# PC_Pump_Controller_2021-02-13_17-24-19.net
KiCad netlist of a schematic drawn in EasyEDA
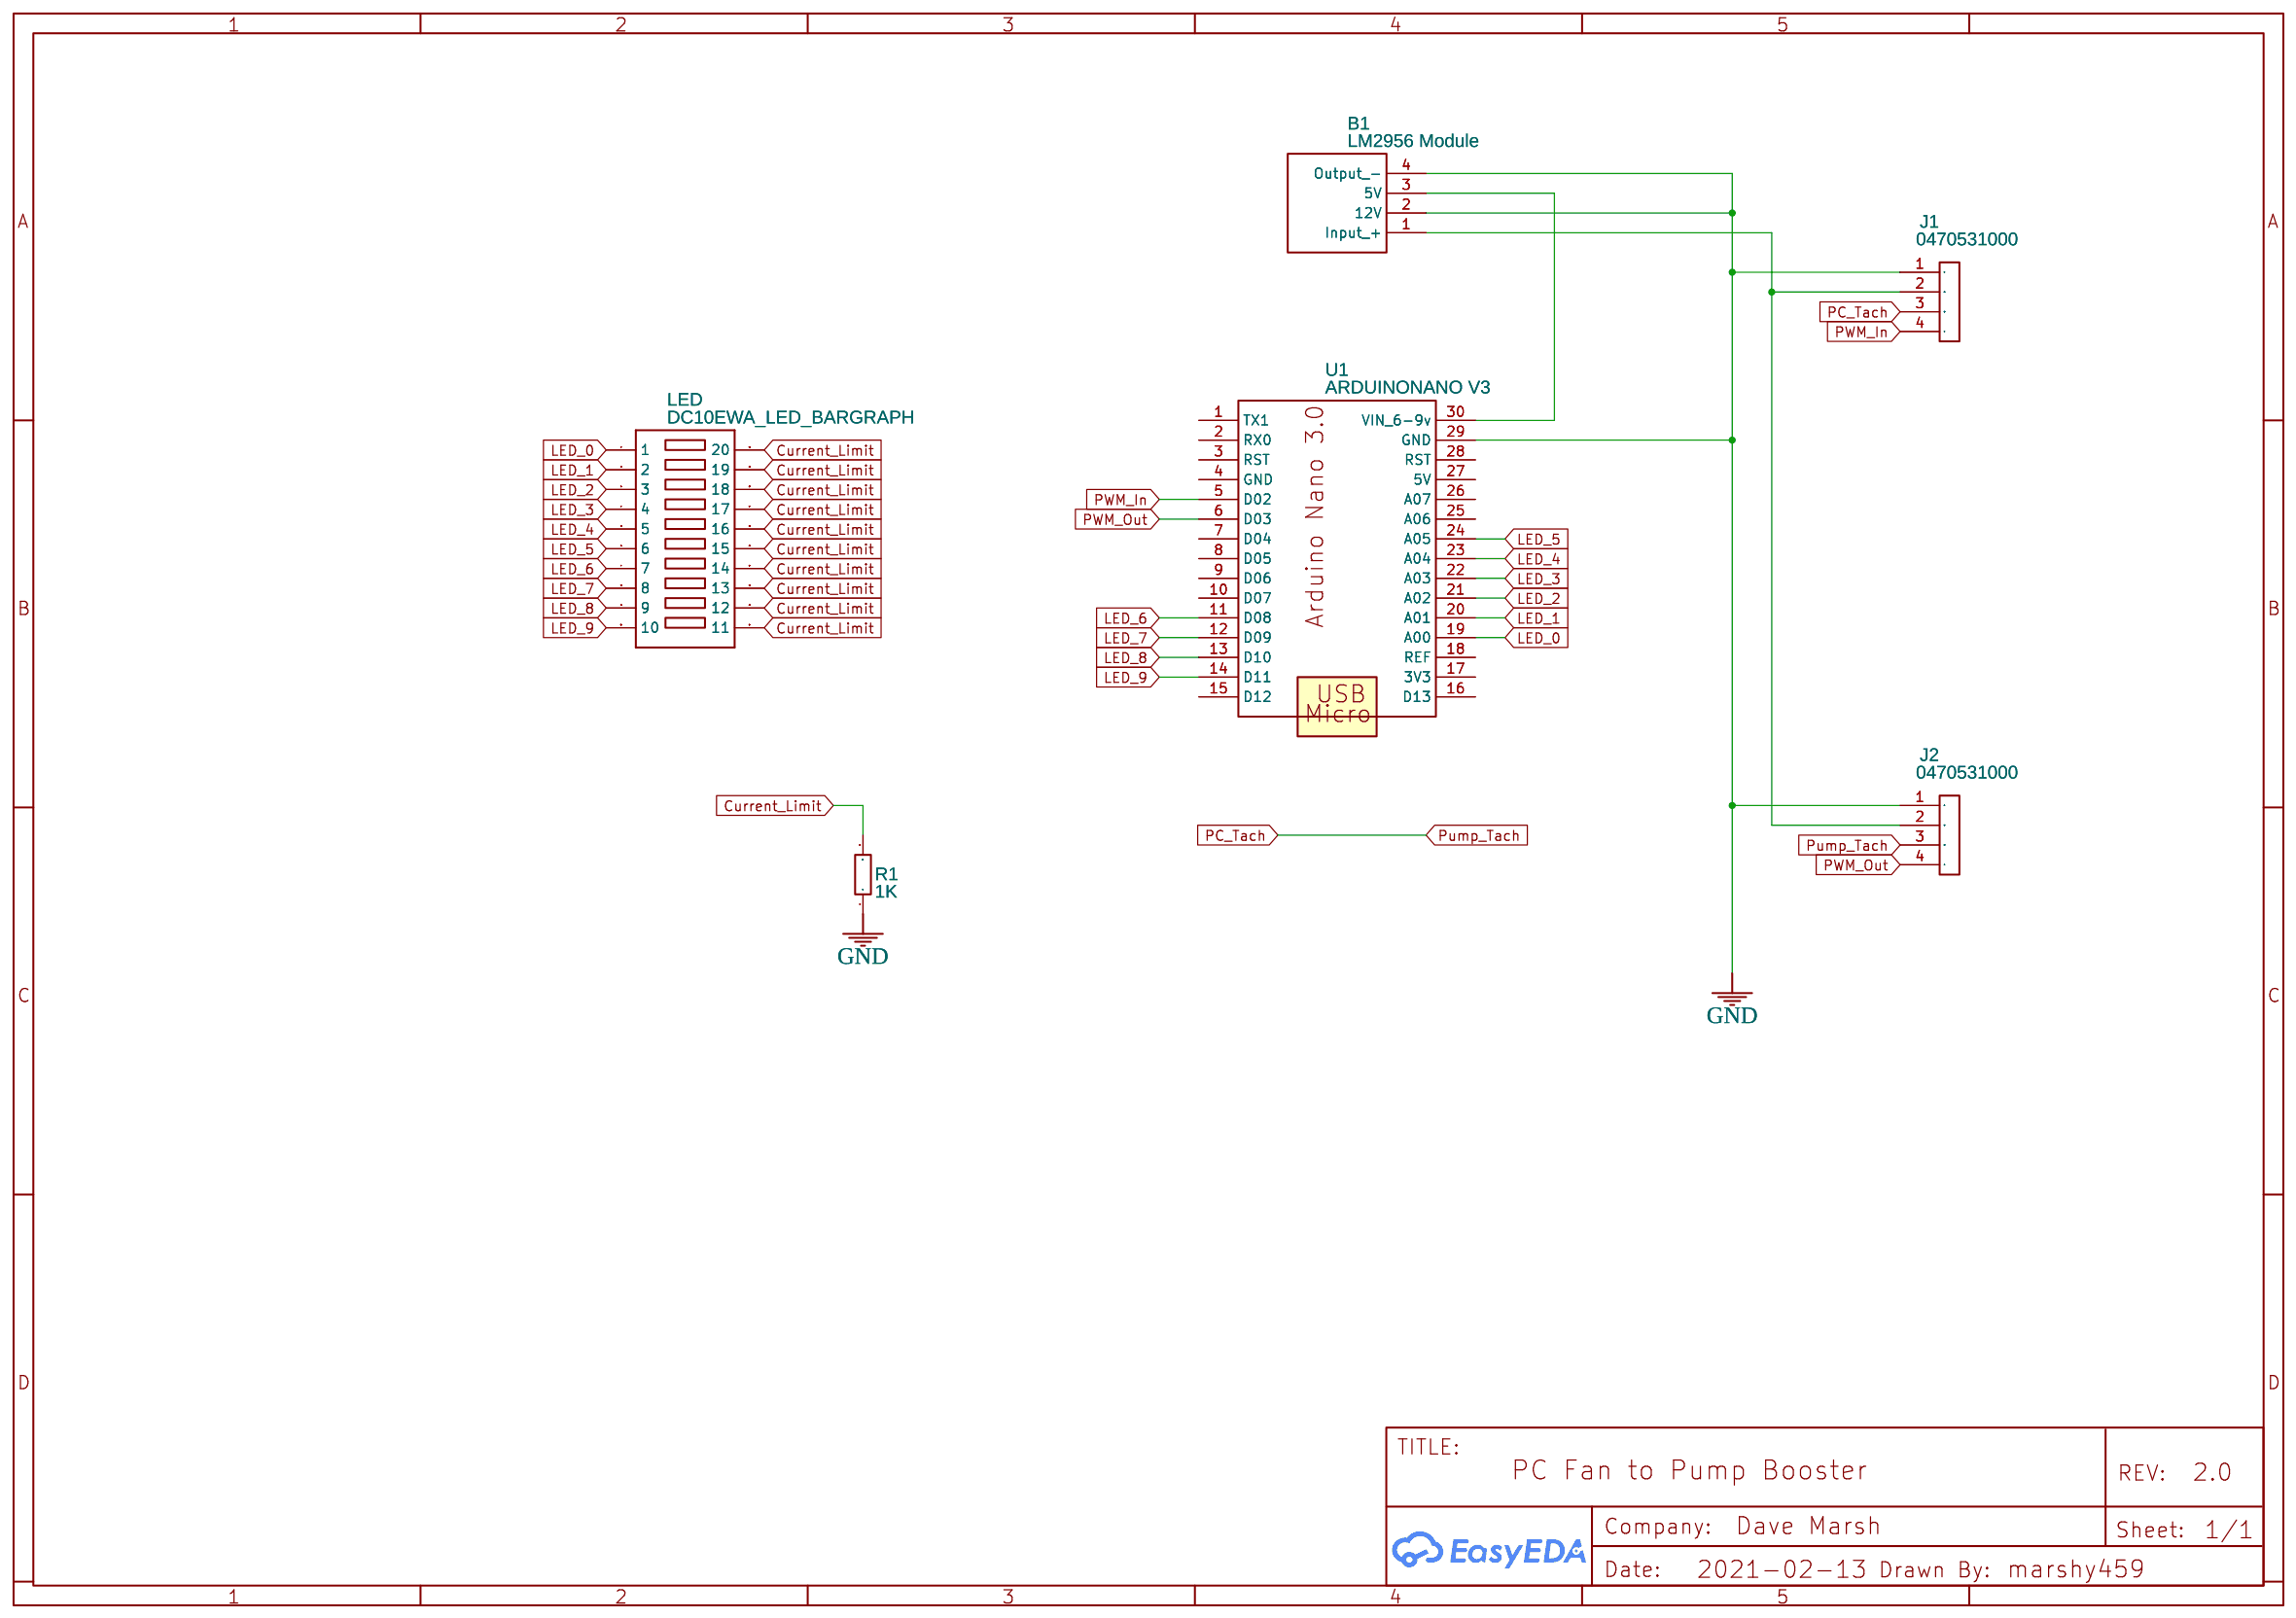
[diagram p0: schematic sheet]

(export (version "E")
  (design (tool "Eeschema 10.0.6"))
  (components
    (comp (ref "B1") (value "LM2956 Module") (libsource (lib "") (part "LM2956 Module")))
    (comp (ref "J1")
      (value "0470531000")
      (fields (field (name "BOM_Supplier Part") "WM4330-ND"))
      (libsource (lib "") (part "0470531000"))
    )
    (comp (ref "J2")
      (value "0470531000")
      (fields (field (name "BOM_Supplier Part") "WM4330-ND"))
      (libsource (lib "") (part "0470531000"))
    )
    (comp (ref "LED") (value "DC10EWA_LED_BARGRAPH") (libsource (lib "") (part "DC10EWA_LED_BARGRAPH")))
    (comp (ref "R1")
      (value "1K")
      (fields
        (field (name "BOM_Manufacturer Part") "RC1206FR-071K5L")
        (field (name "BOM_Supplier Part") "311-1.50KFRCT-ND")
      )
      (libsource (lib "") (part "RESISTOR 1K5 1206 YAGEO"))
    )
    (comp (ref "U1")
      (value "ARDUINONANO V3")
      (fields (field (name "BOM_Manufacturer Part") "ArduinoNanov3"))
      (libsource (lib "") (part "ARDUINONANO V3"))
    )
  )
  (nets
    (net (code "1") (name "Current_Limit") (class "Default")
      (node (ref "LED") (pin "11") (pinfunction "11_11") (pintype "unspecified"))
      (node (ref "LED") (pin "12") (pinfunction "12_12") (pintype "unspecified"))
      (node (ref "LED") (pin "13") (pinfunction "13_13") (pintype "input"))
      (node (ref "LED") (pin "14") (pinfunction "14_14") (pintype "input"))
      (node (ref "LED") (pin "15") (pinfunction "15_15") (pintype "input"))
      (node (ref "LED") (pin "16") (pinfunction "16_16") (pintype "input"))
      (node (ref "LED") (pin "17") (pinfunction "17_17") (pintype "input"))
      (node (ref "LED") (pin "18") (pinfunction "18_18") (pintype "input"))
      (node (ref "LED") (pin "19") (pinfunction "19_19") (pintype "input"))
      (node (ref "LED") (pin "20") (pinfunction "20_20") (pintype "input"))
      (node (ref "R1") (pin "2") (pinfunction "2_2") (pintype "unspecified"))
    )
    (net (code "2") (name "GND") (class "Default")
      (node (ref "B1") (pin "2") (pinfunction "12V_2") (pintype "unspecified"))
      (node (ref "B1") (pin "4") (pinfunction "Output_-_4") (pintype "unspecified"))
      (node (ref "J1") (pin "1") (pinfunction "1_1") (pintype "unspecified"))
      (node (ref "J2") (pin "1") (pinfunction "1_1") (pintype "unspecified"))
      (node (ref "R1") (pin "1") (pinfunction "1_1") (pintype "unspecified"))
      (node (ref "U1") (pin "29") (pinfunction "GND_29") (pintype "unspecified"))
    )
    (net (code "3") (name "LED_0") (class "Default")
      (node (ref "LED") (pin "1") (pinfunction "1_1") (pintype "input"))
      (node (ref "U1") (pin "19") (pinfunction "A00_19") (pintype "unspecified"))
    )
    (net (code "4") (name "LED_1") (class "Default")
      (node (ref "LED") (pin "2") (pinfunction "2_2") (pintype "input"))
      (node (ref "U1") (pin "20") (pinfunction "A01_20") (pintype "unspecified"))
    )
    (net (code "5") (name "LED_2") (class "Default")
      (node (ref "LED") (pin "3") (pinfunction "3_3") (pintype "input"))
      (node (ref "U1") (pin "21") (pinfunction "A02_21") (pintype "unspecified"))
    )
    (net (code "6") (name "LED_3") (class "Default")
      (node (ref "LED") (pin "4") (pinfunction "4_4") (pintype "input"))
      (node (ref "U1") (pin "22") (pinfunction "A03_22") (pintype "unspecified"))
    )
    (net (code "7") (name "LED_4") (class "Default")
      (node (ref "LED") (pin "5") (pinfunction "5_5") (pintype "input"))
      (node (ref "U1") (pin "23") (pinfunction "A04_23") (pintype "unspecified"))
    )
    (net (code "8") (name "LED_5") (class "Default")
      (node (ref "LED") (pin "6") (pinfunction "6_6") (pintype "input"))
      (node (ref "U1") (pin "24") (pinfunction "A05_24") (pintype "unspecified"))
    )
    (net (code "9") (name "LED_6") (class "Default")
      (node (ref "LED") (pin "7") (pinfunction "7_7") (pintype "input"))
      (node (ref "U1") (pin "11") (pinfunction "D08_11") (pintype "unspecified"))
    )
    (net (code "10") (name "LED_7") (class "Default")
      (node (ref "LED") (pin "8") (pinfunction "8_8") (pintype "input"))
      (node (ref "U1") (pin "12") (pinfunction "D09_12") (pintype "unspecified"))
    )
    (net (code "11") (name "LED_8") (class "Default")
      (node (ref "LED") (pin "9") (pinfunction "9_9") (pintype "unspecified"))
      (node (ref "U1") (pin "13") (pinfunction "D10_13") (pintype "unspecified"))
    )
    (net (code "12") (name "LED_9") (class "Default")
      (node (ref "LED") (pin "10") (pinfunction "10_10") (pintype "unspecified"))
      (node (ref "U1") (pin "14") (pinfunction "D11_14") (pintype "unspecified"))
    )
    (net (code "13") (name "Net-(B1-5V)") (class "Default")
      (node (ref "B1") (pin "3") (pinfunction "5V_3") (pintype "unspecified"))
      (node (ref "U1") (pin "30") (pinfunction "VIN_6-9v_30") (pintype "unspecified"))
    )
    (net (code "14") (name "Net-(B1-Input_+)") (class "Default")
      (node (ref "B1") (pin "1") (pinfunction "Input_+_1") (pintype "unspecified"))
      (node (ref "J1") (pin "2") (pinfunction "2_2") (pintype "unspecified"))
      (node (ref "J2") (pin "2") (pinfunction "2_2") (pintype "unspecified"))
    )
    (net (code "15") (name "PC_Tach") (class "Default")
      (node (ref "J1") (pin "3") (pinfunction "3_3") (pintype "unspecified"))
      (node (ref "J2") (pin "3") (pinfunction "3_3") (pintype "unspecified"))
    )
    (net (code "16") (name "PWM_In") (class "Default")
      (node (ref "J1") (pin "4") (pinfunction "4_4") (pintype "unspecified"))
      (node (ref "U1") (pin "5") (pinfunction "D02_5") (pintype "unspecified"))
    )
    (net (code "17") (name "PWM_Out") (class "Default")
      (node (ref "J2") (pin "4") (pinfunction "4_4") (pintype "unspecified"))
      (node (ref "U1") (pin "6") (pinfunction "D03_6") (pintype "unspecified"))
    )
    (net (code "18") (name "unconnected-(U1-3V3-Pad17)") (class "Default")
      (node (ref "U1") (pin "17") (pinfunction "3V3_17") (pintype "unspecified"))
    )
    (net (code "19") (name "unconnected-(U1-5V-Pad27)") (class "Default")
      (node (ref "U1") (pin "27") (pinfunction "5V_27") (pintype "unspecified"))
    )
    (net (code "20") (name "unconnected-(U1-A06-Pad25)") (class "Default")
      (node (ref "U1") (pin "25") (pinfunction "A06_25") (pintype "unspecified"))
    )
    (net (code "21") (name "unconnected-(U1-A07-Pad26)") (class "Default")
      (node (ref "U1") (pin "26") (pinfunction "A07_26") (pintype "unspecified"))
    )
    (net (code "22") (name "unconnected-(U1-D04-Pad7)") (class "Default")
      (node (ref "U1") (pin "7") (pinfunction "D04_7") (pintype "unspecified"))
    )
    (net (code "23") (name "unconnected-(U1-D05-Pad8)") (class "Default")
      (node (ref "U1") (pin "8") (pinfunction "D05_8") (pintype "unspecified"))
    )
    (net (code "24") (name "unconnected-(U1-D06-Pad9)") (class "Default")
      (node (ref "U1") (pin "9") (pinfunction "D06_9") (pintype "unspecified"))
    )
    (net (code "25") (name "unconnected-(U1-D07-Pad10)") (class "Default")
      (node (ref "U1") (pin "10") (pinfunction "D07_10") (pintype "unspecified"))
    )
    (net (code "26") (name "unconnected-(U1-D12-Pad15)") (class "Default")
      (node (ref "U1") (pin "15") (pinfunction "D12_15") (pintype "unspecified"))
    )
    (net (code "27") (name "unconnected-(U1-D13-Pad16)") (class "Default")
      (node (ref "U1") (pin "16") (pinfunction "D13_16") (pintype "unspecified"))
    )
    (net (code "28") (name "unconnected-(U1-GND-Pad4)") (class "Default")
      (node (ref "U1") (pin "4") (pinfunction "GND_4") (pintype "unspecified"))
    )
    (net (code "29") (name "unconnected-(U1-REF-Pad18)") (class "Default")
      (node (ref "U1") (pin "18") (pinfunction "REF_18") (pintype "unspecified"))
    )
    (net (code "30") (name "unconnected-(U1-RST-Pad3)") (class "Default")
      (node (ref "U1") (pin "3") (pinfunction "RST_3") (pintype "unspecified"))
    )
    (net (code "31") (name "unconnected-(U1-RST-Pad28)") (class "Default")
      (node (ref "U1") (pin "28") (pinfunction "RST_28") (pintype "unspecified"))
    )
    (net (code "32") (name "unconnected-(U1-RX0-Pad2)") (class "Default")
      (node (ref "U1") (pin "2") (pinfunction "RX0_2") (pintype "unspecified"))
    )
    (net (code "33") (name "unconnected-(U1-TX1-Pad1)") (class "Default")
      (node (ref "U1") (pin "1") (pinfunction "TX1_1") (pintype "unspecified"))
    )
  )
)
